# LCD.net
KiCad netlist of a schematic drawn in Altium Designer
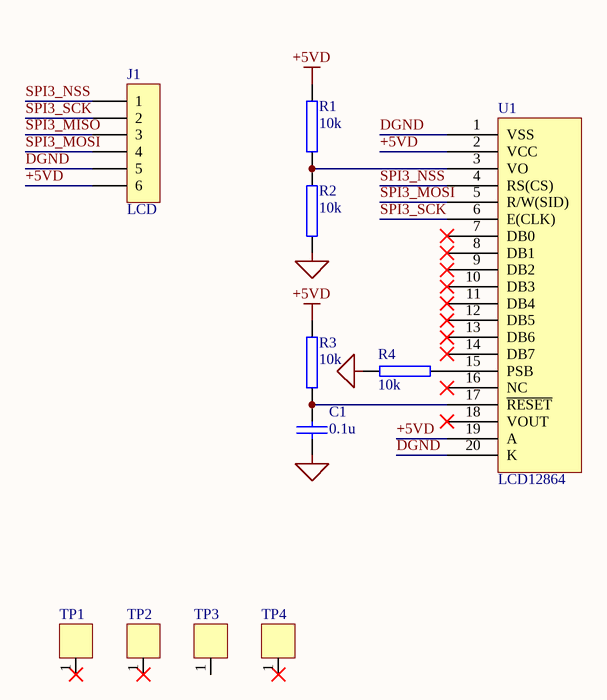
[diagram p0: 故指测试架LCD屏板.SchDoc]

(export (version "E")
  (design (tool "Eeschema 10.0.6"))
  (components
    (comp (ref "C1")
      (value "0.1u")
      (footprint "0805")
      (description "Capacitor")
      (libsource (lib "*") (part "CAP"))
    )
    (comp (ref "J1") (value "LCD") (footprint "2510-6Y") (libsource (lib "主板_1") (part "CON6")))
    (comp (ref "R1") (value "10k") (footprint "0805") (libsource (lib "PCB_Project1") (part "R")))
    (comp (ref "R2") (value "10k") (footprint "0805") (libsource (lib "PCB_Project1") (part "R")))
    (comp (ref "R3") (value "10k") (footprint "0805") (libsource (lib "PCB_Project1") (part "R")))
    (comp (ref "R4") (value "10k") (footprint "0805") (libsource (lib "PCB_Project1") (part "R")))
    (comp (ref "TP1") (value "~") (footprint "PAD4.5") (libsource (lib "*") (part "TESTPT")))
    (comp (ref "TP2") (value "~") (footprint "PAD4.5") (libsource (lib "*") (part "TESTPT")))
    (comp (ref "TP3") (value "~") (footprint "PAD4.5") (libsource (lib "*") (part "TESTPT")))
    (comp (ref "TP4") (value "~") (footprint "PAD4.5") (libsource (lib "*") (part "TESTPT")))
    (comp (ref "U1") (value "LCD12864") (footprint "LCD12864") (libsource (lib "LCD屏板") (part "LCD12864")))
  )
  (nets
    (net (code "1") (name "+5VD") (class "Default")
      (node (ref "J1") (pin "6") (pinfunction "6_6") (pintype "passive"))
      (node (ref "R1") (pin "1") (pinfunction "1_1") (pintype "passive"))
      (node (ref "R3") (pin "1") (pinfunction "1_1") (pintype "passive"))
      (node (ref "U1") (pin "19") (pinfunction "A_19") (pintype "passive"))
      (node (ref "U1") (pin "2") (pinfunction "VCC_2") (pintype "passive"))
    )
    (net (code "2") (name "/SPI3_MISO") (class "Default")
      (node (ref "J1") (pin "3") (pinfunction "3_3") (pintype "passive"))
    )
    (net (code "3") (name "/SPI3_MOSI") (class "Default")
      (node (ref "J1") (pin "4") (pinfunction "4_4") (pintype "passive"))
      (node (ref "U1") (pin "5") (pinfunction "R/W(SID)_5") (pintype "passive"))
    )
    (net (code "4") (name "/SPI3_NSS") (class "Default")
      (node (ref "J1") (pin "1") (pinfunction "1_1") (pintype "passive"))
      (node (ref "U1") (pin "4") (pinfunction "RS(CS)_4") (pintype "passive"))
    )
    (net (code "5") (name "/SPI3_SCK") (class "Default")
      (node (ref "J1") (pin "2") (pinfunction "2_2") (pintype "passive"))
      (node (ref "U1") (pin "6") (pinfunction "E(CLK)_6") (pintype "passive"))
    )
    (net (code "6") (name "DGND") (class "Default")
      (node (ref "C1") (pin "1") (pinfunction "1_1") (pintype "passive"))
      (node (ref "J1") (pin "5") (pinfunction "5_5") (pintype "passive"))
      (node (ref "R2") (pin "2") (pinfunction "2_2") (pintype "passive"))
      (node (ref "R4") (pin "1") (pinfunction "1_1") (pintype "passive"))
      (node (ref "U1") (pin "1") (pinfunction "VSS_1") (pintype "passive"))
      (node (ref "U1") (pin "20") (pinfunction "K_20") (pintype "passive"))
    )
    (net (code "7") (name "Net-(U1-PSB)") (class "Default")
      (node (ref "R4") (pin "2") (pinfunction "2_2") (pintype "passive"))
      (node (ref "U1") (pin "15") (pinfunction "PSB_15") (pintype "passive"))
    )
    (net (code "8") (name "Net-(U1-VO)") (class "Default")
      (node (ref "R1") (pin "2") (pinfunction "2_2") (pintype "passive"))
      (node (ref "R2") (pin "1") (pinfunction "1_1") (pintype "passive"))
      (node (ref "U1") (pin "3") (pinfunction "VO_3") (pintype "passive"))
    )
    (net (code "9") (name "Net-(U1-~{RESET})") (class "Default")
      (node (ref "C1") (pin "2") (pinfunction "2_2") (pintype "passive"))
      (node (ref "R3") (pin "2") (pinfunction "2_2") (pintype "passive"))
      (node (ref "U1") (pin "17") (pinfunction "~{RESET}_17") (pintype "passive"))
    )
    (net (code "10") (name "unconnected-(TP1-Pad1)") (class "Default")
      (node (ref "TP1") (pin "1") (pinfunction "1_1") (pintype "passive+no_connect"))
    )
    (net (code "11") (name "unconnected-(TP2-Pad1)") (class "Default")
      (node (ref "TP2") (pin "1") (pinfunction "1_1") (pintype "passive+no_connect"))
    )
    (net (code "12") (name "unconnected-(TP3-Pad1)") (class "Default")
      (node (ref "TP3") (pin "1") (pinfunction "1_1") (pintype "passive"))
    )
    (net (code "13") (name "unconnected-(TP4-Pad1)") (class "Default")
      (node (ref "TP4") (pin "1") (pinfunction "1_1") (pintype "passive+no_connect"))
    )
    (net (code "14") (name "unconnected-(U1-DB0-Pad7)") (class "Default")
      (node (ref "U1") (pin "7") (pinfunction "DB0_7") (pintype "passive+no_connect"))
    )
    (net (code "15") (name "unconnected-(U1-DB1-Pad8)") (class "Default")
      (node (ref "U1") (pin "8") (pinfunction "DB1_8") (pintype "passive+no_connect"))
    )
    (net (code "16") (name "unconnected-(U1-DB2-Pad9)") (class "Default")
      (node (ref "U1") (pin "9") (pinfunction "DB2_9") (pintype "passive+no_connect"))
    )
    (net (code "17") (name "unconnected-(U1-DB3-Pad10)") (class "Default")
      (node (ref "U1") (pin "10") (pinfunction "DB3_10") (pintype "passive+no_connect"))
    )
    (net (code "18") (name "unconnected-(U1-DB4-Pad11)") (class "Default")
      (node (ref "U1") (pin "11") (pinfunction "DB4_11") (pintype "passive+no_connect"))
    )
    (net (code "19") (name "unconnected-(U1-DB5-Pad12)") (class "Default")
      (node (ref "U1") (pin "12") (pinfunction "DB5_12") (pintype "passive+no_connect"))
    )
    (net (code "20") (name "unconnected-(U1-DB6-Pad13)") (class "Default")
      (node (ref "U1") (pin "13") (pinfunction "DB6_13") (pintype "passive+no_connect"))
    )
    (net (code "21") (name "unconnected-(U1-DB7-Pad14)") (class "Default")
      (node (ref "U1") (pin "14") (pinfunction "DB7_14") (pintype "passive+no_connect"))
    )
    (net (code "22") (name "unconnected-(U1-NC-Pad16)") (class "Default")
      (node (ref "U1") (pin "16") (pinfunction "NC_16") (pintype "passive+no_connect"))
    )
    (net (code "23") (name "unconnected-(U1-VOUT-Pad18)") (class "Default")
      (node (ref "U1") (pin "18") (pinfunction "VOUT_18") (pintype "passive+no_connect"))
    )
  )
)
